# Motor_Driver.net
KiCad netlist of a schematic drawn in Altium Designer
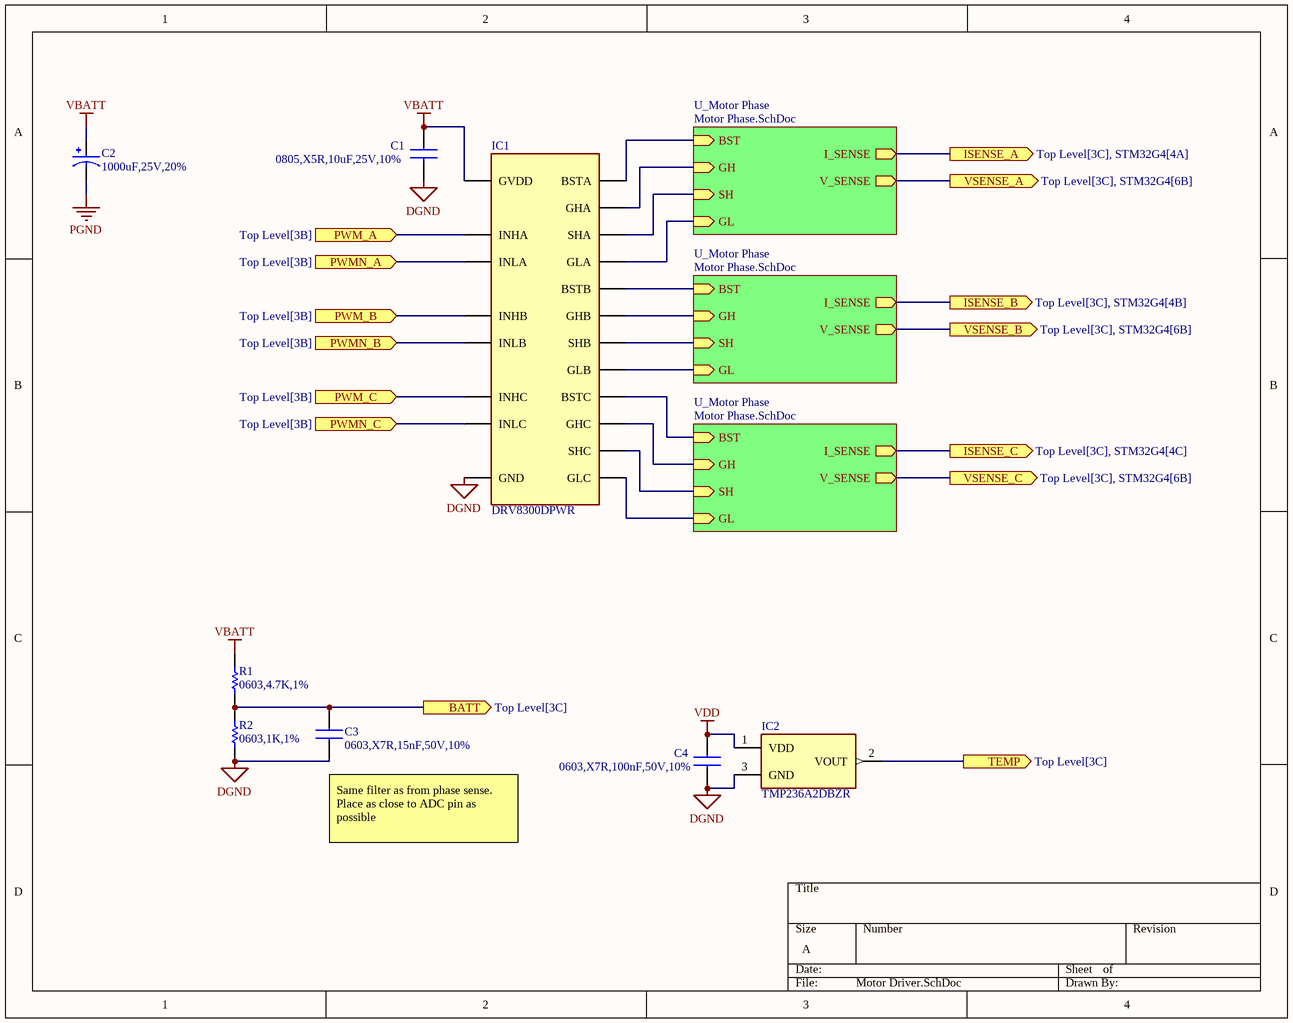
[diagram p0: Motor Driver.SchDoc]

(export (version "E")
  (design (tool "Eeschema 10.0.6"))
  (components
    (comp (ref "C1")
      (value "0805,X5R,10uF,25V,10%")
      (footprint "CAPC2012X145N")
      (description "10 µF ±10% 25V Ceramic Capacitor X5R 0805 (2012 Metric)")
      (fields
        (field (name "MANUFACTURER_PART_NUMBER") "CC0805KKX5R8BB106")
        (field (name "MOUSER PART NUMBER") "603-CC805KKX5R8BB106")
      )
      (libsource (lib "ESC") (part "CC0805KKX5R8BB106"))
    )
    (comp (ref "C2")
      (value "1000uF,25V,20%")
      (footprint "CAP-TH_BD10.0-P5.00-D1.0-FD")
      (description "1000uF 25V ±20% 870mA@120Hz Through Hole,D10xL16mm Aluminum Electrolytic Capacitors - Leaded ROHS")
      (fields (field (name "LCSC PART #") "C109451"))
      (libsource (lib "ESC") (part "25PK1000MEFC10*16"))
    )
    (comp (ref "C3")
      (value "0603,X7R,15nF,50V,10%")
      (footprint "CAPC1608X90N")
      (description "50V 15nF X7R ±10% 0603 Multilayer Ceramic Capacitors MLCC - SMD/SMT ROHS")
      (fields
        (field (name "MANUFACTURER_PART_NUMBER") "CC0603KRX7R9BB153")
        (field (name "MOUSER PART NUMBER") "603-CC603KRX7R9BB104")
      )
      (libsource (lib "ESC") (part "CC0603KRX7R9BB153"))
    )
    (comp (ref "C4")
      (value "0603,X7R,100nF,50V,10%")
      (footprint "CAPC1608X90N")
      (description "50V 100nF X7R ±10% 0603 Multilayer Ceramic Capacitors MLCC - SMD/SMT ROHS")
      (fields
        (field (name "MANUFACTURER_PART_NUMBER") "CC0603KRX7R9BB104")
        (field (name "MOUSER PART NUMBER") "603-CC603KRX7R9BB104")
      )
      (libsource (lib "ESC") (part "CC0603KRX7R9BB104"))
    )
    (comp (ref "IC1")
      (value "DRV8300DPWR")
      (footprint "ESC:SOP65P640X120-20N")
      (description "TSSOP-20 Brushless DC (BLDC) Motor Driver ROHS")
      (fields (field (name "MOUSER PART NUMBER") "595-DRV8300DPWR") (field (name "LCSC PART #") "C3036056"))
      (libsource (lib "ESC") (part "DRV8300DPWR"))
    )
    (comp (ref "IC2")
      (value "TMP236A2DBZR")
      (footprint "SOT95P237X112-3N")
      (description "Low-power and high-precision analog output temperature sensor")
      (fields (field (name "MOUSER PART NUMBER") "595-TMP236A2DBZR") (field (name "LCSC PART #") "C2859666"))
      (libsource (lib "ESC") (part "TMP236A2DBZR"))
    )
    (comp (ref "R1")
      (value "0603,4.7K,1%")
      (footprint "RESC1608X55N")
      (description "100mW Thick Film Resistor 75V ±100ppm/℃ ±1% 4.7kΩ 0603 Chip Resistor - Surface Mount ROHS")
      (fields
        (field (name "MANUFACTURER_PART_NUMBER") "RC0603FR-074K7L")
        (field (name "LCSC PART #") "C99782")
      )
      (libsource (lib "ESC") (part "RC0603FR-074K7L"))
    )
    (comp (ref "R2")
      (value "0603,1K,1%")
      (footprint "RESC1608X55N")
      (description "100mW Thick Film Resistor 75V ±100ppm/℃ ±1% 1kΩ 0603 Chip Resistor - Surface Mount ROHS")
      (fields
        (field (name "MANUFACTURER_PART_NUMBER") "RC0603FR-071KL")
        (field (name "LCSC PART #") "C22548")
      )
      (libsource (lib "ESC") (part "RC0603FR-071KL"))
    )
  )
  (nets
    (net (code "1") (name "/BATT") (class "Default")
      (node (ref "C3") (pin "2") (pinfunction "2_2") (pintype "passive"))
      (node (ref "R1") (pin "1") (pinfunction "1_1") (pintype "passive"))
      (node (ref "R2") (pin "2") (pinfunction "2_2") (pintype "passive"))
    )
    (net (code "2") (name "/BST") (class "Default")
      (node (ref "IC1") (pin "17") (pinfunction "BSTB_17") (pintype "passive"))
    )
    (net (code "3") (name "/BST_1") (class "Default")
      (node (ref "IC1") (pin "14") (pinfunction "BSTC_14") (pintype "passive"))
    )
    (net (code "4") (name "/BST_2") (class "Default")
      (node (ref "IC1") (pin "20") (pinfunction "BSTA_20") (pintype "passive"))
    )
    (net (code "5") (name "/GH") (class "Default")
      (node (ref "IC1") (pin "16") (pinfunction "GHB_16") (pintype "passive"))
    )
    (net (code "6") (name "/GH_1") (class "Default")
      (node (ref "IC1") (pin "13") (pinfunction "GHC_13") (pintype "passive"))
    )
    (net (code "7") (name "/GH_2") (class "Default")
      (node (ref "IC1") (pin "19") (pinfunction "GHA_19") (pintype "passive"))
    )
    (net (code "8") (name "/GL") (class "Default")
      (node (ref "IC1") (pin "10") (pinfunction "GLB_10") (pintype "passive"))
    )
    (net (code "9") (name "/GL_1") (class "Default")
      (node (ref "IC1") (pin "9") (pinfunction "GLC_9") (pintype "passive"))
    )
    (net (code "10") (name "/GL_2") (class "Default")
      (node (ref "IC1") (pin "11") (pinfunction "GLA_11") (pintype "passive"))
    )
    (net (code "14") (name "/PWMN_A") (class "Default")
      (node (ref "IC1") (pin "4") (pinfunction "INLA_4") (pintype "passive"))
    )
    (net (code "15") (name "/PWMN_B") (class "Default")
      (node (ref "IC1") (pin "5") (pinfunction "INLB_5") (pintype "passive"))
    )
    (net (code "16") (name "/PWMN_C") (class "Default")
      (node (ref "IC1") (pin "6") (pinfunction "INLC_6") (pintype "passive"))
    )
    (net (code "17") (name "/PWM_A") (class "Default")
      (node (ref "IC1") (pin "1") (pinfunction "INHA_1") (pintype "passive"))
    )
    (net (code "18") (name "/PWM_B") (class "Default")
      (node (ref "IC1") (pin "2") (pinfunction "INHB_2") (pintype "passive"))
    )
    (net (code "19") (name "/PWM_C") (class "Default")
      (node (ref "IC1") (pin "3") (pinfunction "INHC_3") (pintype "passive"))
    )
    (net (code "20") (name "/SH") (class "Default")
      (node (ref "IC1") (pin "15") (pinfunction "SHB_15") (pintype "passive"))
    )
    (net (code "21") (name "/SH_1") (class "Default")
      (node (ref "IC1") (pin "12") (pinfunction "SHC_12") (pintype "passive"))
    )
    (net (code "22") (name "/SH_2") (class "Default")
      (node (ref "IC1") (pin "18") (pinfunction "SHA_18") (pintype "passive"))
    )
    (net (code "23") (name "/TEMP") (class "Default")
      (node (ref "IC2") (pin "2") (pinfunction "VOUT_2") (pintype "output"))
    )
    (net (code "27") (name "DGND") (class "Default")
      (node (ref "C1") (pin "1") (pinfunction "1_1") (pintype "passive"))
      (node (ref "C3") (pin "1") (pinfunction "1_1") (pintype "passive"))
      (node (ref "C4") (pin "1") (pinfunction "1_1") (pintype "passive"))
      (node (ref "IC1") (pin "8") (pinfunction "GND_8") (pintype "passive"))
      (node (ref "IC2") (pin "3") (pinfunction "GND_3") (pintype "power_in"))
      (node (ref "R2") (pin "1") (pinfunction "1_1") (pintype "passive"))
    )
    (net (code "28") (name "PGND") (class "Default")
      (node (ref "C2") (pin "2") (pinfunction "2_2") (pintype "passive"))
    )
    (net (code "29") (name "VBATT") (class "Default")
      (node (ref "C1") (pin "2") (pinfunction "2_2") (pintype "passive"))
      (node (ref "C2") (pin "1") (pinfunction "1_1") (pintype "passive"))
      (node (ref "IC1") (pin "7") (pinfunction "GVDD_7") (pintype "passive"))
      (node (ref "R1") (pin "2") (pinfunction "2_2") (pintype "passive"))
    )
    (net (code "30") (name "VDD") (class "Default")
      (node (ref "C4") (pin "2") (pinfunction "2_2") (pintype "passive"))
      (node (ref "IC2") (pin "1") (pinfunction "VDD_1") (pintype "power_in"))
    )
  )
)
